# fretscanner-SHIFTREG.net
KiCad netlist of a schematic drawn in EAGLE
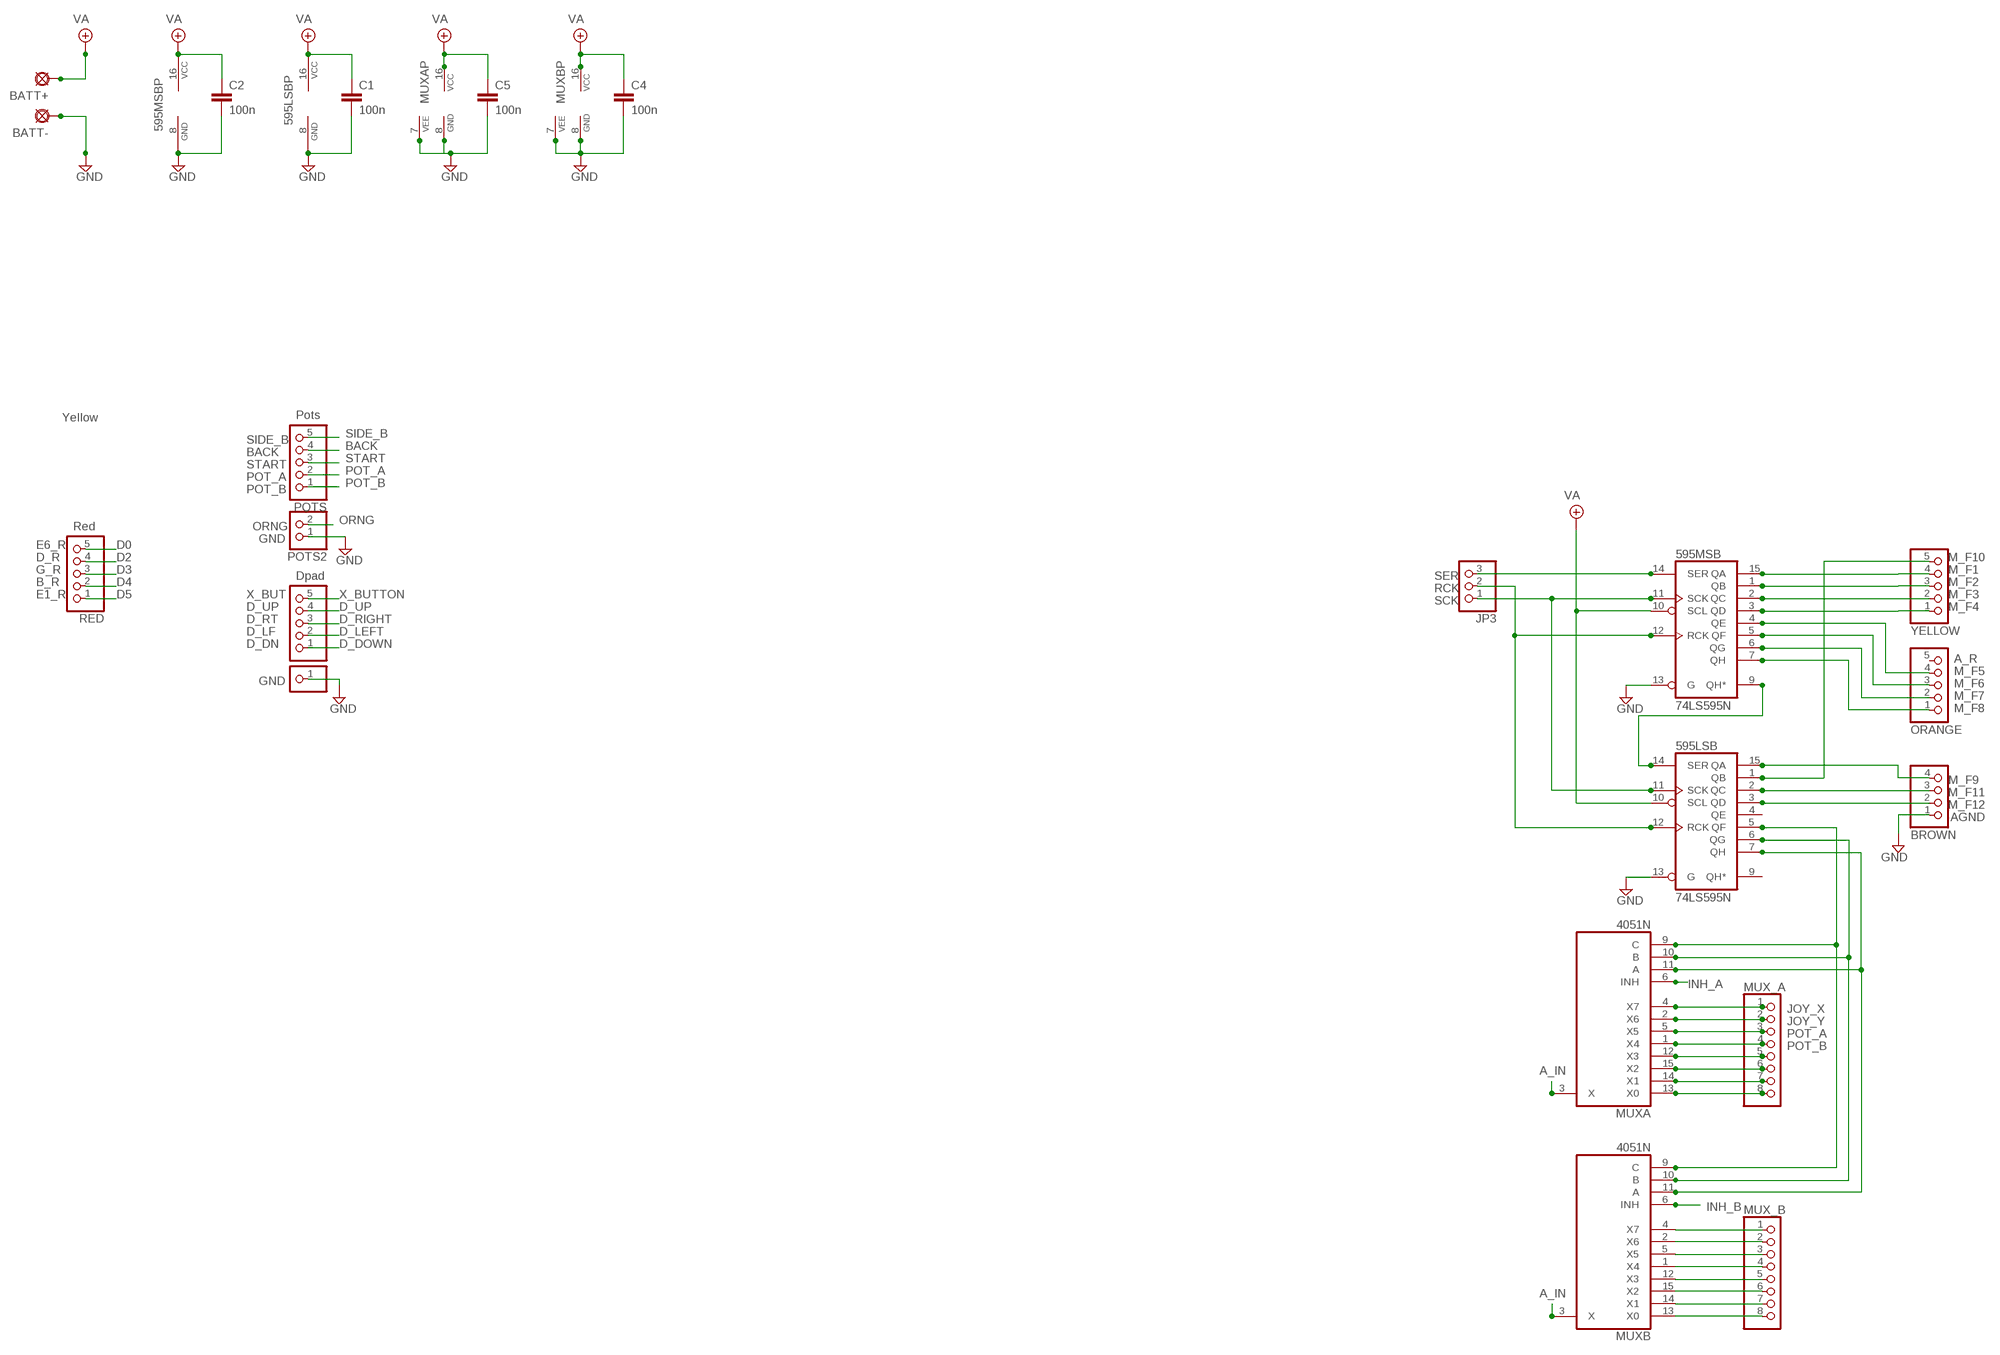
[diagram p0: schematic, sheet 1]

(export (version "E")
  (design (tool "Eeschema 10.0.6"))
  (components
    (comp (ref "595LSB")
      (value "74LS595N")
      (footprint "eagle-import:DIL16")
      (libsource (lib "eagle-import") (part "74595NLS"))
    )
    (comp (ref "595MSB")
      (value "74LS595N")
      (footprint "eagle-import:DIL16")
      (libsource (lib "eagle-import") (part "74595NLS"))
    )
    (comp (ref "BATT+")
      (value "PADL")
      (footprint "eagle-import:LONG")
      (libsource (lib "eagle-import") (part "PADL"))
    )
    (comp (ref "BATT-")
      (value "PADL")
      (footprint "eagle-import:LONG")
      (libsource (lib "eagle-import") (part "PADL"))
    )
    (comp (ref "BROWN")
      (value "PINHD-1X4")
      (footprint "eagle-import:1X04")
      (libsource (lib "eagle-import") (part "PINHD-1X4"))
    )
    (comp (ref "C1")
      (value "100n")
      (footprint "eagle-import:050X030_050_3")
      (libsource (lib "eagle-import") (part "050X030_050"))
    )
    (comp (ref "C2")
      (value "100n")
      (footprint "eagle-import:050X030_050_3")
      (libsource (lib "eagle-import") (part "050X030_050"))
    )
    (comp (ref "C4")
      (value "100n")
      (footprint "eagle-import:050X030_050_3")
      (libsource (lib "eagle-import") (part "050X030_050"))
    )
    (comp (ref "C5")
      (value "100n")
      (footprint "eagle-import:050X030_050_3")
      (libsource (lib "eagle-import") (part "050X030_050"))
    )
    (comp (ref "DPAD")
      (value "PINHD-1X5")
      (footprint "eagle-import:1X05")
      (libsource (lib "eagle-import") (part "PINHD-1X5"))
    )
    (comp (ref "DPAD2")
      (value "PINHD-1X1")
      (footprint "eagle-import:1X01")
      (libsource (lib "eagle-import") (part "PINHD-1X1"))
    )
    (comp (ref "JP3")
      (value "PINHD-1X3")
      (footprint "eagle-import:1X03")
      (libsource (lib "eagle-import") (part "PINHD-1X3"))
    )
    (comp (ref "MUXA")
      (value "4051N")
      (footprint "eagle-import:DIL16")
      (libsource (lib "eagle-import") (part "4051N"))
    )
    (comp (ref "MUXB")
      (value "4051N")
      (footprint "eagle-import:DIL16")
      (libsource (lib "eagle-import") (part "4051N"))
    )
    (comp (ref "MUX_A")
      (value "PINHD-1X8")
      (footprint "eagle-import:1X08")
      (libsource (lib "eagle-import") (part "PINHD-1X8"))
    )
    (comp (ref "MUX_B")
      (value "PINHD-1X8")
      (footprint "eagle-import:1X08")
      (libsource (lib "eagle-import") (part "PINHD-1X8"))
    )
    (comp (ref "ORANGE")
      (value "PINHD-1X5")
      (footprint "eagle-import:1X05")
      (libsource (lib "eagle-import") (part "PINHD-1X5"))
    )
    (comp (ref "POTS")
      (value "PINHD-1X5")
      (footprint "eagle-import:1X05")
      (libsource (lib "eagle-import") (part "PINHD-1X5"))
    )
    (comp (ref "POTS2")
      (value "PINHD-1X2")
      (footprint "eagle-import:1X02")
      (libsource (lib "eagle-import") (part "PINHD-1X2"))
    )
    (comp (ref "RED")
      (value "PINHD-1X5")
      (footprint "eagle-import:1X05")
      (libsource (lib "eagle-import") (part "PINHD-1X5"))
    )
    (comp (ref "YELLOW")
      (value "PINHD-1X5")
      (footprint "eagle-import:1X05")
      (libsource (lib "eagle-import") (part "PINHD-1X5"))
    )
  )
  (nets
    (net (code "1") (name "/A_IN") (class "Default")
      (node (ref "MUXA") (pin "3") (pinfunction "X_3") (pintype "bidirectional"))
      (node (ref "MUXB") (pin "3") (pinfunction "X_3") (pintype "bidirectional"))
    )
    (net (code "2") (name "/BACK") (class "Default")
      (node (ref "POTS") (pin "4") (pinfunction "4_4") (pintype "passive"))
    )
    (net (code "3") (name "/D0") (class "Default")
      (node (ref "RED") (pin "5") (pinfunction "5_5") (pintype "passive"))
    )
    (net (code "4") (name "/D2") (class "Default")
      (node (ref "RED") (pin "4") (pinfunction "4_4") (pintype "passive"))
    )
    (net (code "5") (name "/D3") (class "Default")
      (node (ref "RED") (pin "3") (pinfunction "3_3") (pintype "passive"))
    )
    (net (code "6") (name "/D4") (class "Default")
      (node (ref "RED") (pin "2") (pinfunction "2_2") (pintype "passive"))
    )
    (net (code "7") (name "/D5") (class "Default")
      (node (ref "RED") (pin "1") (pinfunction "1_1") (pintype "passive"))
    )
    (net (code "8") (name "/D_DOWN") (class "Default")
      (node (ref "DPAD") (pin "1") (pinfunction "1_1") (pintype "passive"))
    )
    (net (code "9") (name "/D_LEFT") (class "Default")
      (node (ref "DPAD") (pin "2") (pinfunction "2_2") (pintype "passive"))
    )
    (net (code "10") (name "/D_RIGHT") (class "Default")
      (node (ref "DPAD") (pin "3") (pinfunction "3_3") (pintype "passive"))
    )
    (net (code "11") (name "/D_UP") (class "Default")
      (node (ref "DPAD") (pin "4") (pinfunction "4_4") (pintype "passive"))
    )
    (net (code "12") (name "/INH_A") (class "Default")
      (node (ref "MUXA") (pin "6") (pinfunction "INH_6") (pintype "input"))
    )
    (net (code "13") (name "/INH_B") (class "Default")
      (node (ref "MUXB") (pin "6") (pinfunction "INH_6") (pintype "input"))
    )
    (net (code "14") (name "/JOY_X") (class "Default")
      (node (ref "MUXA") (pin "4") (pinfunction "X7_4") (pintype "bidirectional"))
      (node (ref "MUX_A") (pin "1") (pinfunction "1_1") (pintype "passive"))
    )
    (net (code "15") (name "/JOY_Y") (class "Default")
      (node (ref "MUXA") (pin "2") (pinfunction "X6_2") (pintype "bidirectional"))
      (node (ref "MUX_A") (pin "2") (pinfunction "2_2") (pintype "passive"))
    )
    (net (code "16") (name "/ORNG") (class "Default")
      (node (ref "POTS2") (pin "2") (pinfunction "2_2") (pintype "passive"))
    )
    (net (code "17") (name "/POT_A") (class "Default")
      (node (ref "MUXA") (pin "5") (pinfunction "X5_5") (pintype "bidirectional"))
      (node (ref "MUX_A") (pin "3") (pinfunction "3_3") (pintype "passive"))
      (node (ref "POTS") (pin "2") (pinfunction "2_2") (pintype "passive"))
    )
    (net (code "18") (name "/POT_B") (class "Default")
      (node (ref "MUXA") (pin "1") (pinfunction "X4_1") (pintype "bidirectional"))
      (node (ref "MUX_A") (pin "4") (pinfunction "4_4") (pintype "passive"))
      (node (ref "POTS") (pin "1") (pinfunction "1_1") (pintype "passive"))
    )
    (net (code "19") (name "/RCK") (class "Default")
      (node (ref "595LSB") (pin "12") (pinfunction "RCK_12") (pintype "input"))
      (node (ref "595MSB") (pin "12") (pinfunction "RCK_12") (pintype "input"))
      (node (ref "JP3") (pin "2") (pinfunction "2_2") (pintype "passive"))
    )
    (net (code "20") (name "/SCK") (class "Default")
      (node (ref "595LSB") (pin "11") (pinfunction "SCK_11") (pintype "input"))
      (node (ref "595MSB") (pin "11") (pinfunction "SCK_11") (pintype "input"))
      (node (ref "JP3") (pin "1") (pinfunction "1_1") (pintype "passive"))
    )
    (net (code "21") (name "/SER") (class "Default")
      (node (ref "595MSB") (pin "14") (pinfunction "SER_14") (pintype "input"))
      (node (ref "JP3") (pin "3") (pinfunction "3_3") (pintype "passive"))
    )
    (net (code "22") (name "/SIDE_B") (class "Default")
      (node (ref "POTS") (pin "5") (pinfunction "5_5") (pintype "passive"))
    )
    (net (code "23") (name "/SR12") (class "Default")
      (node (ref "595MSB") (pin "3") (pinfunction "QD_3") (pintype "tri_state"))
      (node (ref "YELLOW") (pin "1") (pinfunction "1_1") (pintype "passive"))
    )
    (net (code "24") (name "/SR13") (class "Default")
      (node (ref "595MSB") (pin "2") (pinfunction "QC_2") (pintype "tri_state"))
      (node (ref "YELLOW") (pin "2") (pinfunction "2_2") (pintype "passive"))
    )
    (net (code "25") (name "/SR14") (class "Default")
      (node (ref "595MSB") (pin "1") (pinfunction "QB_1") (pintype "tri_state"))
      (node (ref "YELLOW") (pin "3") (pinfunction "3_3") (pintype "passive"))
    )
    (net (code "26") (name "/SR15") (class "Default")
      (node (ref "595MSB") (pin "15") (pinfunction "QA_15") (pintype "tri_state"))
      (node (ref "YELLOW") (pin "4") (pinfunction "4_4") (pintype "passive"))
    )
    (net (code "27") (name "/START") (class "Default")
      (node (ref "POTS") (pin "3") (pinfunction "3_3") (pintype "passive"))
    )
    (net (code "28") (name "/X_BUTTON") (class "Default")
      (node (ref "DPAD") (pin "5") (pinfunction "5_5") (pintype "passive"))
    )
    (net (code "29") (name "GND") (class "Default")
      (node (ref "595LSB") (pin "13") (pinfunction "G_13") (pintype "input"))
      (node (ref "595LSB") (pin "8") (pinfunction "GND_8") (pintype "power_in"))
      (node (ref "595MSB") (pin "13") (pinfunction "G_13") (pintype "input"))
      (node (ref "595MSB") (pin "8") (pinfunction "GND_8") (pintype "power_in"))
      (node (ref "BATT-") (pin "1") (pinfunction "PAD_1") (pintype "passive"))
      (node (ref "BROWN") (pin "1") (pinfunction "1_1") (pintype "passive"))
      (node (ref "C1") (pin "2") (pinfunction "2_2") (pintype "passive"))
      (node (ref "C2") (pin "2") (pinfunction "2_2") (pintype "passive"))
      (node (ref "C4") (pin "2") (pinfunction "2_2") (pintype "passive"))
      (node (ref "C5") (pin "2") (pinfunction "2_2") (pintype "passive"))
      (node (ref "DPAD2") (pin "1") (pinfunction "1_1") (pintype "passive"))
      (node (ref "MUXA") (pin "7") (pinfunction "VEE_7") (pintype "power_in"))
      (node (ref "MUXA") (pin "8") (pinfunction "GND_8") (pintype "power_in"))
      (node (ref "MUXB") (pin "7") (pinfunction "VEE_7") (pintype "power_in"))
      (node (ref "MUXB") (pin "8") (pinfunction "GND_8") (pintype "power_in"))
      (node (ref "POTS2") (pin "1") (pinfunction "1_1") (pintype "passive"))
    )
    (net (code "30") (name "Net-(595LSBA-QA)") (class "Default")
      (node (ref "595LSB") (pin "15") (pinfunction "QA_15") (pintype "tri_state"))
      (node (ref "BROWN") (pin "4") (pinfunction "4_4") (pintype "passive"))
    )
    (net (code "31") (name "Net-(595LSBA-QB)") (class "Default")
      (node (ref "595LSB") (pin "1") (pinfunction "QB_1") (pintype "tri_state"))
      (node (ref "YELLOW") (pin "5") (pinfunction "5_5") (pintype "passive"))
    )
    (net (code "32") (name "Net-(595LSBA-QC)") (class "Default")
      (node (ref "595LSB") (pin "2") (pinfunction "QC_2") (pintype "tri_state"))
      (node (ref "BROWN") (pin "3") (pinfunction "3_3") (pintype "passive"))
    )
    (net (code "33") (name "Net-(595LSBA-QD)") (class "Default")
      (node (ref "595LSB") (pin "3") (pinfunction "QD_3") (pintype "tri_state"))
      (node (ref "BROWN") (pin "2") (pinfunction "2_2") (pintype "passive"))
    )
    (net (code "34") (name "Net-(595LSBA-QF)") (class "Default")
      (node (ref "595LSB") (pin "5") (pinfunction "QF_5") (pintype "tri_state"))
      (node (ref "MUXA") (pin "9") (pinfunction "C_9") (pintype "input"))
      (node (ref "MUXB") (pin "9") (pinfunction "C_9") (pintype "input"))
    )
    (net (code "35") (name "Net-(595LSBA-QG)") (class "Default")
      (node (ref "595LSB") (pin "6") (pinfunction "QG_6") (pintype "tri_state"))
      (node (ref "MUXA") (pin "10") (pinfunction "B_10") (pintype "input"))
      (node (ref "MUXB") (pin "10") (pinfunction "B_10") (pintype "input"))
    )
    (net (code "36") (name "Net-(595LSBA-QH)") (class "Default")
      (node (ref "595LSB") (pin "7") (pinfunction "QH_7") (pintype "tri_state"))
      (node (ref "MUXA") (pin "11") (pinfunction "A_11") (pintype "input"))
      (node (ref "MUXB") (pin "11") (pinfunction "A_11") (pintype "input"))
    )
    (net (code "37") (name "Net-(595LSBA-SER)") (class "Default")
      (node (ref "595LSB") (pin "14") (pinfunction "SER_14") (pintype "input"))
      (node (ref "595MSB") (pin "9") (pinfunction "QH*_9") (pintype "tri_state"))
    )
    (net (code "38") (name "Net-(595MSBA-QE)") (class "Default")
      (node (ref "595MSB") (pin "4") (pinfunction "QE_4") (pintype "tri_state"))
      (node (ref "ORANGE") (pin "4") (pinfunction "4_4") (pintype "passive"))
    )
    (net (code "39") (name "Net-(595MSBA-QF)") (class "Default")
      (node (ref "595MSB") (pin "5") (pinfunction "QF_5") (pintype "tri_state"))
      (node (ref "ORANGE") (pin "3") (pinfunction "3_3") (pintype "passive"))
    )
    (net (code "40") (name "Net-(595MSBA-QG)") (class "Default")
      (node (ref "595MSB") (pin "6") (pinfunction "QG_6") (pintype "tri_state"))
      (node (ref "ORANGE") (pin "2") (pinfunction "2_2") (pintype "passive"))
    )
    (net (code "41") (name "Net-(595MSBA-QH)") (class "Default")
      (node (ref "595MSB") (pin "7") (pinfunction "QH_7") (pintype "tri_state"))
      (node (ref "ORANGE") (pin "1") (pinfunction "1_1") (pintype "passive"))
    )
    (net (code "42") (name "Net-(MUXAA-X0)") (class "Default")
      (node (ref "MUXA") (pin "13") (pinfunction "X0_13") (pintype "bidirectional"))
      (node (ref "MUX_A") (pin "8") (pinfunction "8_8") (pintype "passive"))
    )
    (net (code "43") (name "Net-(MUXAA-X1)") (class "Default")
      (node (ref "MUXA") (pin "14") (pinfunction "X1_14") (pintype "bidirectional"))
      (node (ref "MUX_A") (pin "7") (pinfunction "7_7") (pintype "passive"))
    )
    (net (code "44") (name "Net-(MUXAA-X2)") (class "Default")
      (node (ref "MUXA") (pin "15") (pinfunction "X2_15") (pintype "bidirectional"))
      (node (ref "MUX_A") (pin "6") (pinfunction "6_6") (pintype "passive"))
    )
    (net (code "45") (name "Net-(MUXAA-X3)") (class "Default")
      (node (ref "MUXA") (pin "12") (pinfunction "X3_12") (pintype "bidirectional"))
      (node (ref "MUX_A") (pin "5") (pinfunction "5_5") (pintype "passive"))
    )
    (net (code "46") (name "Net-(MUXBA-X0)") (class "Default")
      (node (ref "MUXB") (pin "13") (pinfunction "X0_13") (pintype "bidirectional"))
      (node (ref "MUX_B") (pin "8") (pinfunction "8_8") (pintype "passive"))
    )
    (net (code "47") (name "Net-(MUXBA-X1)") (class "Default")
      (node (ref "MUXB") (pin "14") (pinfunction "X1_14") (pintype "bidirectional"))
      (node (ref "MUX_B") (pin "7") (pinfunction "7_7") (pintype "passive"))
    )
    (net (code "48") (name "Net-(MUXBA-X2)") (class "Default")
      (node (ref "MUXB") (pin "15") (pinfunction "X2_15") (pintype "bidirectional"))
      (node (ref "MUX_B") (pin "6") (pinfunction "6_6") (pintype "passive"))
    )
    (net (code "49") (name "Net-(MUXBA-X3)") (class "Default")
      (node (ref "MUXB") (pin "12") (pinfunction "X3_12") (pintype "bidirectional"))
      (node (ref "MUX_B") (pin "5") (pinfunction "5_5") (pintype "passive"))
    )
    (net (code "50") (name "Net-(MUXBA-X4)") (class "Default")
      (node (ref "MUXB") (pin "1") (pinfunction "X4_1") (pintype "bidirectional"))
      (node (ref "MUX_B") (pin "4") (pinfunction "4_4") (pintype "passive"))
    )
    (net (code "51") (name "Net-(MUXBA-X5)") (class "Default")
      (node (ref "MUXB") (pin "5") (pinfunction "X5_5") (pintype "bidirectional"))
      (node (ref "MUX_B") (pin "3") (pinfunction "3_3") (pintype "passive"))
    )
    (net (code "52") (name "Net-(MUXBA-X6)") (class "Default")
      (node (ref "MUXB") (pin "2") (pinfunction "X6_2") (pintype "bidirectional"))
      (node (ref "MUX_B") (pin "2") (pinfunction "2_2") (pintype "passive"))
    )
    (net (code "53") (name "Net-(MUXBA-X7)") (class "Default")
      (node (ref "MUXB") (pin "4") (pinfunction "X7_4") (pintype "bidirectional"))
      (node (ref "MUX_B") (pin "1") (pinfunction "1_1") (pintype "passive"))
    )
    (net (code "54") (name "VA") (class "Default")
      (node (ref "595LSB") (pin "10") (pinfunction "SCL_10") (pintype "input"))
      (node (ref "595LSB") (pin "16") (pinfunction "VCC_16") (pintype "power_in"))
      (node (ref "595MSB") (pin "10") (pinfunction "SCL_10") (pintype "input"))
      (node (ref "595MSB") (pin "16") (pinfunction "VCC_16") (pintype "power_in"))
      (node (ref "BATT+") (pin "1") (pinfunction "PAD_1") (pintype "passive"))
      (node (ref "C1") (pin "1") (pinfunction "1_1") (pintype "passive"))
      (node (ref "C2") (pin "1") (pinfunction "1_1") (pintype "passive"))
      (node (ref "C4") (pin "1") (pinfunction "1_1") (pintype "passive"))
      (node (ref "C5") (pin "1") (pinfunction "1_1") (pintype "passive"))
      (node (ref "MUXA") (pin "16") (pinfunction "VCC_16") (pintype "power_in"))
      (node (ref "MUXB") (pin "16") (pinfunction "VCC_16") (pintype "power_in"))
    )
    (net (code "55") (name "unconnected-(595LSBA-QE-Pad4)") (class "Default")
      (node (ref "595LSB") (pin "4") (pinfunction "QE_4") (pintype "tri_state"))
    )
    (net (code "56") (name "unconnected-(595LSBA-QH*-Pad9)") (class "Default")
      (node (ref "595LSB") (pin "9") (pinfunction "QH*_9") (pintype "tri_state"))
    )
    (net (code "57") (name "unconnected-(ORANGE-Pad5)") (class "Default")
      (node (ref "ORANGE") (pin "5") (pinfunction "5_5") (pintype "passive"))
    )
  )
)
